# Opto_Circuits.net
KiCad netlist of a schematic drawn in Altium Designer
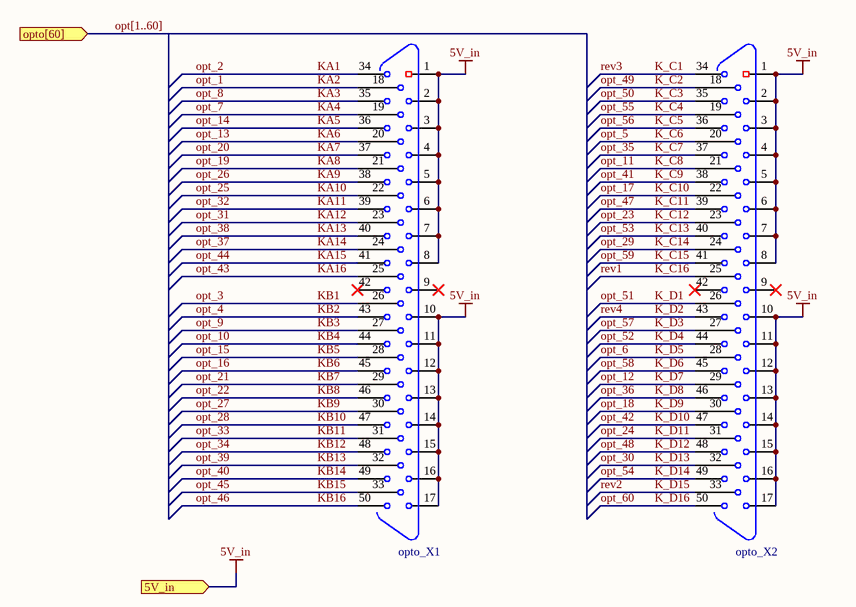
[diagram p0: Opto_Circuits.SchDoc]

(export (version "E")
  (design (tool "Eeschema 10.0.6"))
  (components
    (comp (ref "opto_X1") (value "DB50") (footprint "DB50_RA") (libsource (lib "WIRE") (part "DB50")))
    (comp (ref "opto_X2") (value "DB50") (footprint "DB50_RA") (libsource (lib "WIRE") (part "DB50")))
  )
  (nets
    (net (code "61") (name "/KA1") (class "Default")
      (node (ref "opto_X1") (pin "34") (pinfunction "34_34") (pintype "passive"))
    )
    (net (code "62") (name "/KA2") (class "Default")
      (node (ref "opto_X1") (pin "18") (pinfunction "18_18") (pintype "passive"))
    )
    (net (code "63") (name "/KA3") (class "Default")
      (node (ref "opto_X1") (pin "35") (pinfunction "35_35") (pintype "passive"))
    )
    (net (code "64") (name "/KA4") (class "Default")
      (node (ref "opto_X1") (pin "19") (pinfunction "19_19") (pintype "passive"))
    )
    (net (code "65") (name "/KA5") (class "Default")
      (node (ref "opto_X1") (pin "36") (pinfunction "36_36") (pintype "passive"))
    )
    (net (code "66") (name "/KA6") (class "Default")
      (node (ref "opto_X1") (pin "20") (pinfunction "20_20") (pintype "passive"))
    )
    (net (code "67") (name "/KA7") (class "Default")
      (node (ref "opto_X1") (pin "37") (pinfunction "37_37") (pintype "passive"))
    )
    (net (code "68") (name "/KA8") (class "Default")
      (node (ref "opto_X1") (pin "21") (pinfunction "21_21") (pintype "passive"))
    )
    (net (code "69") (name "/KA9") (class "Default")
      (node (ref "opto_X1") (pin "38") (pinfunction "38_38") (pintype "passive"))
    )
    (net (code "70") (name "/KA10") (class "Default")
      (node (ref "opto_X1") (pin "22") (pinfunction "22_22") (pintype "passive"))
    )
    (net (code "71") (name "/KA11") (class "Default")
      (node (ref "opto_X1") (pin "39") (pinfunction "39_39") (pintype "passive"))
    )
    (net (code "72") (name "/KA12") (class "Default")
      (node (ref "opto_X1") (pin "23") (pinfunction "23_23") (pintype "passive"))
    )
    (net (code "73") (name "/KA13") (class "Default")
      (node (ref "opto_X1") (pin "40") (pinfunction "40_40") (pintype "passive"))
    )
    (net (code "74") (name "/KA14") (class "Default")
      (node (ref "opto_X1") (pin "24") (pinfunction "7_24") (pintype "passive"))
    )
    (net (code "75") (name "/KA15") (class "Default")
      (node (ref "opto_X1") (pin "41") (pinfunction "41_41") (pintype "passive"))
    )
    (net (code "76") (name "/KA16") (class "Default")
      (node (ref "opto_X1") (pin "25") (pinfunction "3_25") (pintype "passive"))
    )
    (net (code "77") (name "/KB1") (class "Default")
      (node (ref "opto_X1") (pin "26") (pinfunction "26_26") (pintype "passive"))
    )
    (net (code "78") (name "/KB2") (class "Default")
      (node (ref "opto_X1") (pin "43") (pinfunction "43_43") (pintype "passive"))
    )
    (net (code "79") (name "/KB3") (class "Default")
      (node (ref "opto_X1") (pin "27") (pinfunction "27_27") (pintype "passive"))
    )
    (net (code "80") (name "/KB4") (class "Default")
      (node (ref "opto_X1") (pin "44") (pinfunction "44_44") (pintype "passive"))
    )
    (net (code "81") (name "/KB5") (class "Default")
      (node (ref "opto_X1") (pin "28") (pinfunction "28_28") (pintype "passive"))
    )
    (net (code "82") (name "/KB6") (class "Default")
      (node (ref "opto_X1") (pin "45") (pinfunction "45_45") (pintype "passive"))
    )
    (net (code "83") (name "/KB7") (class "Default")
      (node (ref "opto_X1") (pin "29") (pinfunction "29_29") (pintype "passive"))
    )
    (net (code "84") (name "/KB8") (class "Default")
      (node (ref "opto_X1") (pin "46") (pinfunction "46_46") (pintype "passive"))
    )
    (net (code "85") (name "/KB9") (class "Default")
      (node (ref "opto_X1") (pin "30") (pinfunction "30_30") (pintype "passive"))
    )
    (net (code "86") (name "/KB10") (class "Default")
      (node (ref "opto_X1") (pin "47") (pinfunction "47_47") (pintype "passive"))
    )
    (net (code "87") (name "/KB11") (class "Default")
      (node (ref "opto_X1") (pin "31") (pinfunction "31_31") (pintype "passive"))
    )
    (net (code "88") (name "/KB12") (class "Default")
      (node (ref "opto_X1") (pin "48") (pinfunction "48_48") (pintype "passive"))
    )
    (net (code "89") (name "/KB13") (class "Default")
      (node (ref "opto_X1") (pin "32") (pinfunction "32_32") (pintype "passive"))
    )
    (net (code "90") (name "/KB14") (class "Default")
      (node (ref "opto_X1") (pin "49") (pinfunction "49_49") (pintype "passive"))
    )
    (net (code "91") (name "/KB15") (class "Default")
      (node (ref "opto_X1") (pin "33") (pinfunction "33_33") (pintype "passive"))
    )
    (net (code "92") (name "/KB16") (class "Default")
      (node (ref "opto_X1") (pin "50") (pinfunction "50_50") (pintype "passive"))
    )
    (net (code "93") (name "/K_C1") (class "Default")
      (node (ref "opto_X2") (pin "34") (pinfunction "34_34") (pintype "passive"))
    )
    (net (code "94") (name "/K_C2") (class "Default")
      (node (ref "opto_X2") (pin "18") (pinfunction "18_18") (pintype "passive"))
    )
    (net (code "95") (name "/K_C3") (class "Default")
      (node (ref "opto_X2") (pin "35") (pinfunction "35_35") (pintype "passive"))
    )
    (net (code "96") (name "/K_C4") (class "Default")
      (node (ref "opto_X2") (pin "19") (pinfunction "19_19") (pintype "passive"))
    )
    (net (code "97") (name "/K_C5") (class "Default")
      (node (ref "opto_X2") (pin "36") (pinfunction "36_36") (pintype "passive"))
    )
    (net (code "98") (name "/K_C6") (class "Default")
      (node (ref "opto_X2") (pin "20") (pinfunction "20_20") (pintype "passive"))
    )
    (net (code "99") (name "/K_C7") (class "Default")
      (node (ref "opto_X2") (pin "37") (pinfunction "37_37") (pintype "passive"))
    )
    (net (code "100") (name "/K_C8") (class "Default")
      (node (ref "opto_X2") (pin "21") (pinfunction "21_21") (pintype "passive"))
    )
    (net (code "101") (name "/K_C9") (class "Default")
      (node (ref "opto_X2") (pin "38") (pinfunction "38_38") (pintype "passive"))
    )
    (net (code "102") (name "/K_C10") (class "Default")
      (node (ref "opto_X2") (pin "22") (pinfunction "22_22") (pintype "passive"))
    )
    (net (code "103") (name "/K_C11") (class "Default")
      (node (ref "opto_X2") (pin "39") (pinfunction "39_39") (pintype "passive"))
    )
    (net (code "104") (name "/K_C12") (class "Default")
      (node (ref "opto_X2") (pin "23") (pinfunction "23_23") (pintype "passive"))
    )
    (net (code "105") (name "/K_C13") (class "Default")
      (node (ref "opto_X2") (pin "40") (pinfunction "40_40") (pintype "passive"))
    )
    (net (code "106") (name "/K_C14") (class "Default")
      (node (ref "opto_X2") (pin "24") (pinfunction "7_24") (pintype "passive"))
    )
    (net (code "107") (name "/K_C15") (class "Default")
      (node (ref "opto_X2") (pin "41") (pinfunction "41_41") (pintype "passive"))
    )
    (net (code "108") (name "/K_C16") (class "Default")
      (node (ref "opto_X2") (pin "25") (pinfunction "3_25") (pintype "passive"))
    )
    (net (code "109") (name "/K_D1") (class "Default")
      (node (ref "opto_X2") (pin "26") (pinfunction "26_26") (pintype "passive"))
    )
    (net (code "110") (name "/K_D2") (class "Default")
      (node (ref "opto_X2") (pin "43") (pinfunction "43_43") (pintype "passive"))
    )
    (net (code "111") (name "/K_D3") (class "Default")
      (node (ref "opto_X2") (pin "27") (pinfunction "27_27") (pintype "passive"))
    )
    (net (code "112") (name "/K_D4") (class "Default")
      (node (ref "opto_X2") (pin "44") (pinfunction "44_44") (pintype "passive"))
    )
    (net (code "113") (name "/K_D5") (class "Default")
      (node (ref "opto_X2") (pin "28") (pinfunction "28_28") (pintype "passive"))
    )
    (net (code "114") (name "/K_D6") (class "Default")
      (node (ref "opto_X2") (pin "45") (pinfunction "45_45") (pintype "passive"))
    )
    (net (code "115") (name "/K_D7") (class "Default")
      (node (ref "opto_X2") (pin "29") (pinfunction "29_29") (pintype "passive"))
    )
    (net (code "116") (name "/K_D8") (class "Default")
      (node (ref "opto_X2") (pin "46") (pinfunction "46_46") (pintype "passive"))
    )
    (net (code "117") (name "/K_D9") (class "Default")
      (node (ref "opto_X2") (pin "30") (pinfunction "30_30") (pintype "passive"))
    )
    (net (code "118") (name "/K_D10") (class "Default")
      (node (ref "opto_X2") (pin "47") (pinfunction "47_47") (pintype "passive"))
    )
    (net (code "119") (name "/K_D11") (class "Default")
      (node (ref "opto_X2") (pin "31") (pinfunction "31_31") (pintype "passive"))
    )
    (net (code "120") (name "/K_D12") (class "Default")
      (node (ref "opto_X2") (pin "48") (pinfunction "48_48") (pintype "passive"))
    )
    (net (code "121") (name "/K_D13") (class "Default")
      (node (ref "opto_X2") (pin "32") (pinfunction "32_32") (pintype "passive"))
    )
    (net (code "122") (name "/K_D14") (class "Default")
      (node (ref "opto_X2") (pin "49") (pinfunction "49_49") (pintype "passive"))
    )
    (net (code "123") (name "/K_D15") (class "Default")
      (node (ref "opto_X2") (pin "33") (pinfunction "33_33") (pintype "passive"))
    )
    (net (code "124") (name "/K_D16") (class "Default")
      (node (ref "opto_X2") (pin "50") (pinfunction "50_50") (pintype "passive"))
    )
    (net (code "126") (name "5V_in") (class "Default")
      (node (ref "opto_X1") (pin "1") (pinfunction "1_1") (pintype "passive"))
      (node (ref "opto_X1") (pin "10") (pinfunction "10_10") (pintype "passive"))
      (node (ref "opto_X1") (pin "11") (pinfunction "11_11") (pintype "passive"))
      (node (ref "opto_X1") (pin "12") (pinfunction "12_12") (pintype "passive"))
      (node (ref "opto_X1") (pin "13") (pinfunction "13_13") (pintype "passive"))
      (node (ref "opto_X1") (pin "14") (pinfunction "14_14") (pintype "passive"))
      (node (ref "opto_X1") (pin "15") (pinfunction "15_15") (pintype "passive"))
      (node (ref "opto_X1") (pin "16") (pinfunction "16_16") (pintype "passive"))
      (node (ref "opto_X1") (pin "17") (pinfunction "17_17") (pintype "passive"))
      (node (ref "opto_X1") (pin "2") (pinfunction "2_2") (pintype "passive"))
      (node (ref "opto_X1") (pin "3") (pinfunction "3_3") (pintype "passive"))
      (node (ref "opto_X1") (pin "4") (pinfunction "4_4") (pintype "passive"))
      (node (ref "opto_X1") (pin "5") (pinfunction "2_5") (pintype "passive"))
      (node (ref "opto_X1") (pin "6") (pinfunction "6_6") (pintype "passive"))
      (node (ref "opto_X1") (pin "7") (pinfunction "7_7") (pintype "passive"))
      (node (ref "opto_X1") (pin "8") (pinfunction "8_8") (pintype "passive"))
      (node (ref "opto_X2") (pin "1") (pinfunction "1_1") (pintype "passive"))
      (node (ref "opto_X2") (pin "10") (pinfunction "10_10") (pintype "passive"))
      (node (ref "opto_X2") (pin "11") (pinfunction "11_11") (pintype "passive"))
      (node (ref "opto_X2") (pin "12") (pinfunction "12_12") (pintype "passive"))
      (node (ref "opto_X2") (pin "13") (pinfunction "13_13") (pintype "passive"))
      (node (ref "opto_X2") (pin "14") (pinfunction "14_14") (pintype "passive"))
      (node (ref "opto_X2") (pin "15") (pinfunction "15_15") (pintype "passive"))
      (node (ref "opto_X2") (pin "16") (pinfunction "16_16") (pintype "passive"))
      (node (ref "opto_X2") (pin "17") (pinfunction "17_17") (pintype "passive"))
      (node (ref "opto_X2") (pin "2") (pinfunction "2_2") (pintype "passive"))
      (node (ref "opto_X2") (pin "3") (pinfunction "3_3") (pintype "passive"))
      (node (ref "opto_X2") (pin "4") (pinfunction "4_4") (pintype "passive"))
      (node (ref "opto_X2") (pin "5") (pinfunction "2_5") (pintype "passive"))
      (node (ref "opto_X2") (pin "6") (pinfunction "6_6") (pintype "passive"))
      (node (ref "opto_X2") (pin "7") (pinfunction "7_7") (pintype "passive"))
      (node (ref "opto_X2") (pin "8") (pinfunction "8_8") (pintype "passive"))
    )
    (net (code "127") (name "unconnected-(opto_X1-4-Pad9)") (class "Default")
      (node (ref "opto_X1") (pin "9") (pinfunction "4_9") (pintype "passive+no_connect"))
    )
    (net (code "128") (name "unconnected-(opto_X1-Pad42)") (class "Default")
      (node (ref "opto_X1") (pin "42") (pinfunction "42_42") (pintype "passive+no_connect"))
    )
    (net (code "129") (name "unconnected-(opto_X2-4-Pad9)") (class "Default")
      (node (ref "opto_X2") (pin "9") (pinfunction "4_9") (pintype "passive+no_connect"))
    )
    (net (code "130") (name "unconnected-(opto_X2-Pad42)") (class "Default")
      (node (ref "opto_X2") (pin "42") (pinfunction "42_42") (pintype "passive+no_connect"))
    )
  )
)
